# untitled.net
KiCad netlist of a schematic drawn in EAGLE
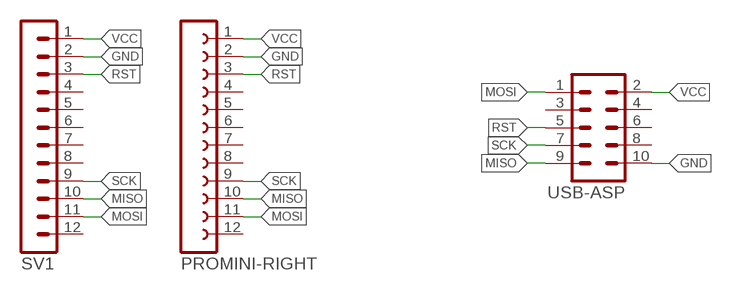
[diagram p0: schematic, sheet 1]

(export (version "E")
  (design (tool "Eeschema 10.0.6"))
  (components
    (comp (ref "PROMINI-RIGHT")
      (value "FE12-1")
      (footprint "eagle-import:FE12")
      (libsource (lib "eagle-import") (part "FE12-1"))
    )
    (comp (ref "SV1")
      (value "MA12-1")
      (footprint "eagle-import:MA12-1")
      (libsource (lib "eagle-import") (part "MA12-1"))
    )
    (comp (ref "USB-ASP")
      (value "MA05-2")
      (footprint "eagle-import:MA05-2")
      (libsource (lib "eagle-import") (part "MA05-2"))
    )
  )
  (nets
    (net (code "1") (name "GND") (class "Default")
      (node (ref "PROMINI-RIGHT") (pin "2") (pinfunction "2_2") (pintype "passive"))
      (node (ref "SV1") (pin "2") (pinfunction "2_2") (pintype "passive"))
      (node (ref "USB-ASP") (pin "10") (pinfunction "10_10") (pintype "passive"))
    )
    (net (code "2") (name "MISO") (class "Default")
      (node (ref "PROMINI-RIGHT") (pin "10") (pinfunction "10_10") (pintype "passive"))
      (node (ref "SV1") (pin "10") (pinfunction "10_10") (pintype "passive"))
      (node (ref "USB-ASP") (pin "9") (pinfunction "9_9") (pintype "passive"))
    )
    (net (code "3") (name "MOSI") (class "Default")
      (node (ref "PROMINI-RIGHT") (pin "11") (pinfunction "11_11") (pintype "passive"))
      (node (ref "SV1") (pin "11") (pinfunction "11_11") (pintype "passive"))
      (node (ref "USB-ASP") (pin "1") (pinfunction "1_1") (pintype "passive"))
    )
    (net (code "4") (name "RST") (class "Default")
      (node (ref "PROMINI-RIGHT") (pin "3") (pinfunction "3_3") (pintype "passive"))
      (node (ref "SV1") (pin "3") (pinfunction "3_3") (pintype "passive"))
      (node (ref "USB-ASP") (pin "5") (pinfunction "5_5") (pintype "passive"))
    )
    (net (code "5") (name "SCK") (class "Default")
      (node (ref "PROMINI-RIGHT") (pin "9") (pinfunction "9_9") (pintype "passive"))
      (node (ref "SV1") (pin "9") (pinfunction "9_9") (pintype "passive"))
      (node (ref "USB-ASP") (pin "7") (pinfunction "7_7") (pintype "passive"))
    )
    (net (code "6") (name "VCC") (class "Default")
      (node (ref "PROMINI-RIGHT") (pin "1") (pinfunction "1_1") (pintype "passive"))
      (node (ref "SV1") (pin "1") (pinfunction "1_1") (pintype "passive"))
      (node (ref "USB-ASP") (pin "2") (pinfunction "2_2") (pintype "passive"))
    )
    (net (code "7") (name "unconnected-(PROMINI-RIGHT-Pad4)") (class "Default")
      (node (ref "PROMINI-RIGHT") (pin "4") (pinfunction "4_4") (pintype "passive"))
    )
    (net (code "8") (name "unconnected-(PROMINI-RIGHT-Pad5)") (class "Default")
      (node (ref "PROMINI-RIGHT") (pin "5") (pinfunction "5_5") (pintype "passive"))
    )
    (net (code "9") (name "unconnected-(PROMINI-RIGHT-Pad6)") (class "Default")
      (node (ref "PROMINI-RIGHT") (pin "6") (pinfunction "6_6") (pintype "passive"))
    )
    (net (code "10") (name "unconnected-(PROMINI-RIGHT-Pad7)") (class "Default")
      (node (ref "PROMINI-RIGHT") (pin "7") (pinfunction "7_7") (pintype "passive"))
    )
    (net (code "11") (name "unconnected-(PROMINI-RIGHT-Pad8)") (class "Default")
      (node (ref "PROMINI-RIGHT") (pin "8") (pinfunction "8_8") (pintype "passive"))
    )
    (net (code "12") (name "unconnected-(PROMINI-RIGHT-Pad12)") (class "Default")
      (node (ref "PROMINI-RIGHT") (pin "12") (pinfunction "12_12") (pintype "passive"))
    )
    (net (code "13") (name "unconnected-(SV1-Pad4)") (class "Default")
      (node (ref "SV1") (pin "4") (pinfunction "4_4") (pintype "passive"))
    )
    (net (code "14") (name "unconnected-(SV1-Pad5)") (class "Default")
      (node (ref "SV1") (pin "5") (pinfunction "5_5") (pintype "passive"))
    )
    (net (code "15") (name "unconnected-(SV1-Pad6)") (class "Default")
      (node (ref "SV1") (pin "6") (pinfunction "6_6") (pintype "passive"))
    )
    (net (code "16") (name "unconnected-(SV1-Pad7)") (class "Default")
      (node (ref "SV1") (pin "7") (pinfunction "7_7") (pintype "passive"))
    )
    (net (code "17") (name "unconnected-(SV1-Pad8)") (class "Default")
      (node (ref "SV1") (pin "8") (pinfunction "8_8") (pintype "passive"))
    )
    (net (code "18") (name "unconnected-(SV1-Pad12)") (class "Default")
      (node (ref "SV1") (pin "12") (pinfunction "12_12") (pintype "passive"))
    )
    (net (code "19") (name "unconnected-(USB-ASP-Pad3)") (class "Default")
      (node (ref "USB-ASP") (pin "3") (pinfunction "3_3") (pintype "passive"))
    )
    (net (code "20") (name "unconnected-(USB-ASP-Pad4)") (class "Default")
      (node (ref "USB-ASP") (pin "4") (pinfunction "4_4") (pintype "passive"))
    )
    (net (code "21") (name "unconnected-(USB-ASP-Pad6)") (class "Default")
      (node (ref "USB-ASP") (pin "6") (pinfunction "6_6") (pintype "passive"))
    )
    (net (code "22") (name "unconnected-(USB-ASP-Pad8)") (class "Default")
      (node (ref "USB-ASP") (pin "8") (pinfunction "8_8") (pintype "passive"))
    )
  )
)
